# Mircophone_Module_Sch_9-8-21.net
KiCad netlist of a schematic drawn in Altium Designer
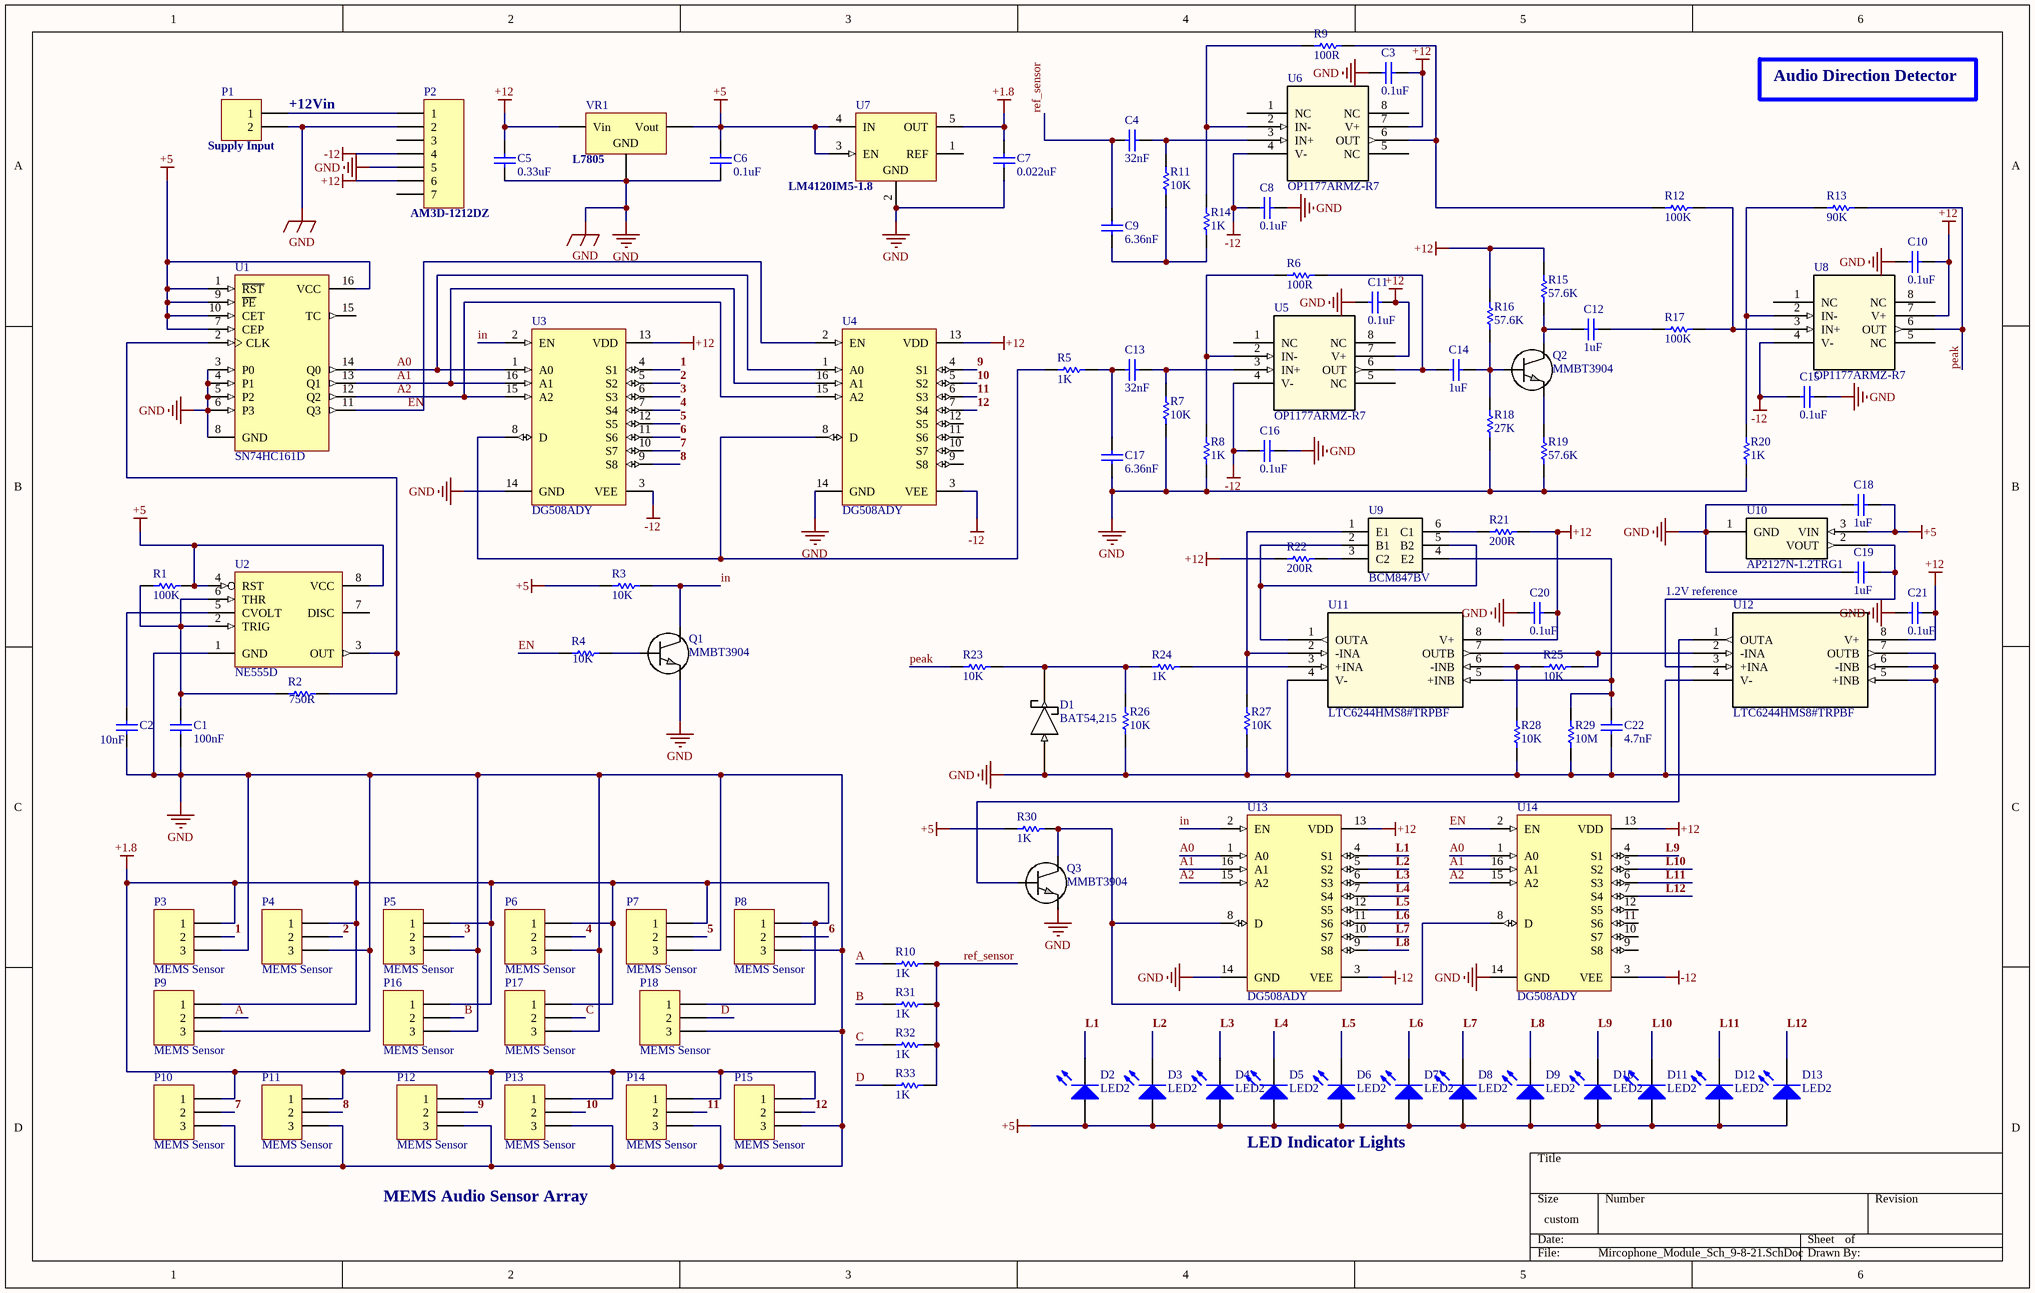
[diagram p0: Mircophone_Module_Sch_9-8-21.SchDoc]

(export (version "E")
  (design (tool "Eeschema 10.0.6"))
  (components
    (comp (ref "C1")
      (value "100nF")
      (footprint "C1206")
      (fields (field (name "PUBLISHER") "Altium Limited"))
      (libsource (lib "Miscellaneous Devices") (part "Cap Semi"))
    )
    (comp (ref "C2")
      (value "10nF")
      (footprint "C1206")
      (fields (field (name "PUBLISHER") "Altium Limited"))
      (libsource (lib "Miscellaneous Devices") (part "Cap Semi"))
    )
    (comp (ref "C3")
      (value "0.1uF")
      (footprint "C1206")
      (fields (field (name "PUBLISHER") "Altium Limited"))
      (libsource (lib "Miscellaneous Devices") (part "Cap Semi"))
    )
    (comp (ref "C4")
      (value "32nF")
      (footprint "C1206")
      (fields (field (name "PUBLISHER") "Altium Limited"))
      (libsource (lib "Miscellaneous Devices") (part "Cap Semi"))
    )
    (comp (ref "C5")
      (value "0.33uF")
      (footprint "C1206")
      (fields (field (name "PUBLISHER") "Altium Limited"))
      (libsource (lib "Miscellaneous Devices") (part "Cap Semi"))
    )
    (comp (ref "C6")
      (value "0.1uF")
      (footprint "C1206")
      (fields (field (name "PUBLISHER") "Altium Limited"))
      (libsource (lib "Miscellaneous Devices") (part "Cap Semi"))
    )
    (comp (ref "C7")
      (value "0.022uF")
      (footprint "C1206")
      (fields (field (name "PUBLISHER") "Altium Limited"))
      (libsource (lib "Miscellaneous Devices") (part "Cap Semi"))
    )
    (comp (ref "C8")
      (value "0.1uF")
      (footprint "C1206")
      (fields (field (name "PUBLISHER") "Altium Limited"))
      (libsource (lib "Miscellaneous Devices") (part "Cap Semi"))
    )
    (comp (ref "C9")
      (value "6.36nF")
      (footprint "C1206")
      (fields (field (name "PUBLISHER") "Altium Limited"))
      (libsource (lib "Miscellaneous Devices") (part "Cap Semi"))
    )
    (comp (ref "C10")
      (value "0.1uF")
      (footprint "C1206")
      (fields (field (name "PUBLISHER") "Altium Limited"))
      (libsource (lib "Miscellaneous Devices") (part "Cap Semi"))
    )
    (comp (ref "C11")
      (value "0.1uF")
      (footprint "C1206")
      (fields (field (name "PUBLISHER") "Altium Limited"))
      (libsource (lib "Miscellaneous Devices") (part "Cap Semi"))
    )
    (comp (ref "C12")
      (value "1uF")
      (footprint "C1206")
      (fields (field (name "PUBLISHER") "Altium Limited"))
      (libsource (lib "Miscellaneous Devices") (part "Cap Semi"))
    )
    (comp (ref "C13")
      (value "32nF")
      (footprint "C1206")
      (fields (field (name "PUBLISHER") "Altium Limited"))
      (libsource (lib "Miscellaneous Devices") (part "Cap Semi"))
    )
    (comp (ref "C14")
      (value "1uF")
      (footprint "C1206")
      (fields (field (name "PUBLISHER") "Altium Limited"))
      (libsource (lib "Miscellaneous Devices") (part "Cap Semi"))
    )
    (comp (ref "C15")
      (value "0.1uF")
      (footprint "C1206")
      (fields (field (name "PUBLISHER") "Altium Limited"))
      (libsource (lib "Miscellaneous Devices") (part "Cap Semi"))
    )
    (comp (ref "C16")
      (value "0.1uF")
      (footprint "C1206")
      (fields (field (name "PUBLISHER") "Altium Limited"))
      (libsource (lib "Miscellaneous Devices") (part "Cap Semi"))
    )
    (comp (ref "C17")
      (value "6.36nF")
      (footprint "C1206")
      (fields (field (name "PUBLISHER") "Altium Limited"))
      (libsource (lib "Miscellaneous Devices") (part "Cap Semi"))
    )
    (comp (ref "C18")
      (value "1uF")
      (footprint "C1206")
      (fields (field (name "PUBLISHER") "Altium Limited"))
      (libsource (lib "Miscellaneous Devices") (part "Cap Semi"))
    )
    (comp (ref "C19")
      (value "1uF")
      (footprint "C1206")
      (fields (field (name "PUBLISHER") "Altium Limited"))
      (libsource (lib "Miscellaneous Devices") (part "Cap Semi"))
    )
    (comp (ref "C20")
      (value "0.1uF")
      (footprint "C1206")
      (fields (field (name "PUBLISHER") "Altium Limited"))
      (libsource (lib "Miscellaneous Devices") (part "Cap Semi"))
    )
    (comp (ref "C21")
      (value "0.1uF")
      (footprint "C1206")
      (fields (field (name "PUBLISHER") "Altium Limited"))
      (libsource (lib "Miscellaneous Devices") (part "Cap Semi"))
    )
    (comp (ref "C22")
      (value "4.7nF")
      (footprint "C1206")
      (fields (field (name "PUBLISHER") "Altium Limited"))
      (libsource (lib "Miscellaneous Devices") (part "Cap Semi"))
    )
    (comp (ref "D1")
      (value "BAT54,215")
      (footprint "SOT95P230X110-3N")
      (description "No Description Available")
      (fields (field (name "COPYRIGHT") "Copyright (C) 2021 Ultra Librarian. All rights reserved."))
      (libsource (lib "BAT54,215") (part "BAT54,215"))
    )
    (comp (ref "D2")
      (value "LED2")
      (footprint "0603")
      (description "Typical RED, GREEN, YELLOW, AMBER GaAs LED")
      (fields (field (name "PUBLISHER") "Altium Limited"))
      (libsource (lib "Miscellaneous Devices") (part "LED2"))
    )
    (comp (ref "D3")
      (value "LED2")
      (footprint "0603")
      (description "Typical RED, GREEN, YELLOW, AMBER GaAs LED")
      (fields (field (name "PUBLISHER") "Altium Limited"))
      (libsource (lib "Miscellaneous Devices") (part "LED2"))
    )
    (comp (ref "D4")
      (value "LED2")
      (footprint "0603")
      (description "Typical RED, GREEN, YELLOW, AMBER GaAs LED")
      (fields (field (name "PUBLISHER") "Altium Limited"))
      (libsource (lib "Miscellaneous Devices") (part "LED2"))
    )
    (comp (ref "D5")
      (value "LED2")
      (footprint "0603")
      (description "Typical RED, GREEN, YELLOW, AMBER GaAs LED")
      (fields (field (name "PUBLISHER") "Altium Limited"))
      (libsource (lib "Miscellaneous Devices") (part "LED2"))
    )
    (comp (ref "D6")
      (value "LED2")
      (footprint "0603")
      (description "Typical RED, GREEN, YELLOW, AMBER GaAs LED")
      (fields (field (name "PUBLISHER") "Altium Limited"))
      (libsource (lib "Miscellaneous Devices") (part "LED2"))
    )
    (comp (ref "D7")
      (value "LED2")
      (footprint "0603")
      (description "Typical RED, GREEN, YELLOW, AMBER GaAs LED")
      (fields (field (name "PUBLISHER") "Altium Limited"))
      (libsource (lib "Miscellaneous Devices") (part "LED2"))
    )
    (comp (ref "D8")
      (value "LED2")
      (footprint "0603")
      (description "Typical RED, GREEN, YELLOW, AMBER GaAs LED")
      (fields (field (name "PUBLISHER") "Altium Limited"))
      (libsource (lib "Miscellaneous Devices") (part "LED2"))
    )
    (comp (ref "D9")
      (value "LED2")
      (footprint "0603")
      (description "Typical RED, GREEN, YELLOW, AMBER GaAs LED")
      (fields (field (name "PUBLISHER") "Altium Limited"))
      (libsource (lib "Miscellaneous Devices") (part "LED2"))
    )
    (comp (ref "D10")
      (value "LED2")
      (footprint "0603")
      (description "Typical RED, GREEN, YELLOW, AMBER GaAs LED")
      (fields (field (name "PUBLISHER") "Altium Limited"))
      (libsource (lib "Miscellaneous Devices") (part "LED2"))
    )
    (comp (ref "D11")
      (value "LED2")
      (footprint "0603")
      (description "Typical RED, GREEN, YELLOW, AMBER GaAs LED")
      (fields (field (name "PUBLISHER") "Altium Limited"))
      (libsource (lib "Miscellaneous Devices") (part "LED2"))
    )
    (comp (ref "D12")
      (value "LED2")
      (footprint "0603")
      (description "Typical RED, GREEN, YELLOW, AMBER GaAs LED")
      (fields (field (name "PUBLISHER") "Altium Limited"))
      (libsource (lib "Miscellaneous Devices") (part "LED2"))
    )
    (comp (ref "D13")
      (value "LED2")
      (footprint "0603")
      (description "Typical RED, GREEN, YELLOW, AMBER GaAs LED")
      (fields (field (name "PUBLISHER") "Altium Limited"))
      (libsource (lib "Miscellaneous Devices") (part "LED2"))
    )
    (comp (ref "P1")
      (value "Supply Input")
      (footprint "HDR1X2")
      (description "Header, 2-Pin")
      (fields (field (name "PUBLISHER") "Altium Limited"))
      (libsource (lib "Miscellaneous Connectors") (part "Header 2"))
    )
    (comp (ref "P2")
      (value "AM3D-1212DZ")
      (footprint "HDR1X7")
      (description "3 Watt ¦ DC-DC Converter Dual 1000VDC isolation")
      (fields (field (name "PUBLISHER") "Altium Limited"))
      (libsource (lib "Miscellaneous Connectors") (part "Header 7"))
    )
    (comp (ref "P3")
      (value "MEMS Sensor")
      (footprint "MIC_ICS-43434")
      (description "MMICT4076-00-908")
      (fields (field (name "PUBLISHER") "Altium Limited"))
      (libsource (lib "Miscellaneous Connectors") (part "Header 3"))
    )
    (comp (ref "P4")
      (value "MEMS Sensor")
      (footprint "MIC_ICS-43434")
      (description "MMICT4076-00-908")
      (fields (field (name "PUBLISHER") "Altium Limited"))
      (libsource (lib "Miscellaneous Connectors") (part "Header 3"))
    )
    (comp (ref "P5")
      (value "MEMS Sensor")
      (footprint "MIC_ICS-43434")
      (description "MMICT4076-00-908")
      (fields (field (name "PUBLISHER") "Altium Limited"))
      (libsource (lib "Miscellaneous Connectors") (part "Header 3"))
    )
    (comp (ref "P6")
      (value "MEMS Sensor")
      (footprint "MIC_ICS-43434")
      (description "MMICT4076-00-908")
      (fields (field (name "PUBLISHER") "Altium Limited"))
      (libsource (lib "Miscellaneous Connectors") (part "Header 3"))
    )
    (comp (ref "P7")
      (value "MEMS Sensor")
      (footprint "MIC_ICS-43434")
      (description "MMICT4076-00-908")
      (fields (field (name "PUBLISHER") "Altium Limited"))
      (libsource (lib "Miscellaneous Connectors") (part "Header 3"))
    )
    (comp (ref "P8")
      (value "MEMS Sensor")
      (footprint "MIC_ICS-43434")
      (description "MMICT4076-00-908")
      (fields (field (name "PUBLISHER") "Altium Limited"))
      (libsource (lib "Miscellaneous Connectors") (part "Header 3"))
    )
    (comp (ref "P9")
      (value "MEMS Sensor")
      (footprint "MIC_ICS-43434")
      (description "MMICT4076-00-908")
      (fields (field (name "PUBLISHER") "Altium Limited"))
      (libsource (lib "Miscellaneous Connectors") (part "Header 3"))
    )
    (comp (ref "P10")
      (value "MEMS Sensor")
      (footprint "MIC_ICS-43434")
      (description "MMICT4076-00-908")
      (fields (field (name "PUBLISHER") "Altium Limited"))
      (libsource (lib "Miscellaneous Connectors") (part "Header 3"))
    )
    (comp (ref "P11")
      (value "MEMS Sensor")
      (footprint "MIC_ICS-43434")
      (description "MMICT4076-00-908")
      (fields (field (name "PUBLISHER") "Altium Limited"))
      (libsource (lib "Miscellaneous Connectors") (part "Header 3"))
    )
    (comp (ref "P12")
      (value "MEMS Sensor")
      (footprint "MIC_ICS-43434")
      (description "MMICT4076-00-908")
      (fields (field (name "PUBLISHER") "Altium Limited"))
      (libsource (lib "Miscellaneous Connectors") (part "Header 3"))
    )
    (comp (ref "P13")
      (value "MEMS Sensor")
      (footprint "MIC_ICS-43434")
      (description "MMICT4076-00-908")
      (fields (field (name "PUBLISHER") "Altium Limited"))
      (libsource (lib "Miscellaneous Connectors") (part "Header 3"))
    )
    (comp (ref "P14")
      (value "MEMS Sensor")
      (footprint "MIC_ICS-43434")
      (description "MMICT4076-00-908")
      (fields (field (name "PUBLISHER") "Altium Limited"))
      (libsource (lib "Miscellaneous Connectors") (part "Header 3"))
    )
    (comp (ref "P15")
      (value "MEMS Sensor")
      (footprint "MIC_ICS-43434")
      (description "MMICT4076-00-908")
      (fields (field (name "PUBLISHER") "Altium Limited"))
      (libsource (lib "Miscellaneous Connectors") (part "Header 3"))
    )
    (comp (ref "P16")
      (value "MEMS Sensor")
      (footprint "MIC_ICS-43434")
      (description "MMICT4076-00-908")
      (fields (field (name "PUBLISHER") "Altium Limited"))
      (libsource (lib "Miscellaneous Connectors") (part "Header 3"))
    )
    (comp (ref "P17")
      (value "MEMS Sensor")
      (footprint "MIC_ICS-43434")
      (description "MMICT4076-00-908")
      (fields (field (name "PUBLISHER") "Altium Limited"))
      (libsource (lib "Miscellaneous Connectors") (part "Header 3"))
    )
    (comp (ref "P18")
      (value "MEMS Sensor")
      (footprint "MIC_ICS-43434")
      (description "MMICT4076-00-908")
      (fields (field (name "PUBLISHER") "Altium Limited"))
      (libsource (lib "Miscellaneous Connectors") (part "Header 3"))
    )
    (comp (ref "Q1")
      (value "MMBT3904")
      (footprint "SOT95P230X110-3N")
      (description "No Description Available")
      (fields (field (name "COPYRIGHT") "Copyright (C) 2021 Ultra Librarian. All rights reserved."))
      (libsource (lib "MMBT3904") (part "MMBT3904"))
    )
    (comp (ref "Q2")
      (value "MMBT3904")
      (footprint "SOT95P230X110-3N")
      (description "No Description Available")
      (fields (field (name "COPYRIGHT") "Copyright (C) 2021 Ultra Librarian. All rights reserved."))
      (libsource (lib "MMBT3904") (part "MMBT3904"))
    )
    (comp (ref "Q3")
      (value "MMBT3904")
      (footprint "SOT95P230X110-3N")
      (description "No Description Available")
      (fields (field (name "COPYRIGHT") "Copyright (C) 2021 Ultra Librarian. All rights reserved."))
      (libsource (lib "MMBT3904") (part "MMBT3904"))
    )
    (comp (ref "R1")
      (value "100K")
      (footprint "6-0805_N")
      (description "Resistor")
      (fields (field (name "PUBLISHER") "Altium Limited"))
      (libsource (lib "Miscellaneous Devices") (part "Res1"))
    )
    (comp (ref "R2")
      (value "750R")
      (footprint "6-0805_N")
      (description "Resistor")
      (fields (field (name "PUBLISHER") "Altium Limited"))
      (libsource (lib "Miscellaneous Devices") (part "Res1"))
    )
    (comp (ref "R3")
      (value "10K")
      (footprint "6-0805_N")
      (description "Resistor")
      (fields (field (name "PUBLISHER") "Altium Limited"))
      (libsource (lib "Miscellaneous Devices") (part "Res1"))
    )
    (comp (ref "R4")
      (value "10K")
      (footprint "6-0805_N")
      (description "Resistor")
      (fields (field (name "PUBLISHER") "Altium Limited"))
      (libsource (lib "Miscellaneous Devices") (part "Res1"))
    )
    (comp (ref "R5")
      (value "1K")
      (footprint "6-0805_N")
      (description "Resistor")
      (fields (field (name "PUBLISHER") "Altium Limited"))
      (libsource (lib "Miscellaneous Devices") (part "Res1"))
    )
    (comp (ref "R6")
      (value "100R")
      (footprint "6-0805_N")
      (description "Resistor")
      (fields (field (name "PUBLISHER") "Altium Limited"))
      (libsource (lib "Miscellaneous Devices") (part "Res1"))
    )
    (comp (ref "R7")
      (value "10K")
      (footprint "6-0805_N")
      (description "Resistor")
      (fields (field (name "PUBLISHER") "Altium Limited"))
      (libsource (lib "Miscellaneous Devices") (part "Res1"))
    )
    (comp (ref "R8")
      (value "1K")
      (footprint "6-0805_N")
      (description "Resistor")
      (fields (field (name "PUBLISHER") "Altium Limited"))
      (libsource (lib "Miscellaneous Devices") (part "Res1"))
    )
    (comp (ref "R9")
      (value "100R")
      (footprint "6-0805_N")
      (description "Resistor")
      (fields (field (name "PUBLISHER") "Altium Limited"))
      (libsource (lib "Miscellaneous Devices") (part "Res1"))
    )
    (comp (ref "R10")
      (value "1K")
      (footprint "6-0805_N")
      (description "Resistor")
      (fields (field (name "PUBLISHER") "Altium Limited"))
      (libsource (lib "Miscellaneous Devices") (part "Res1"))
    )
    (comp (ref "R11")
      (value "10K")
      (footprint "6-0805_N")
      (description "Resistor")
      (fields (field (name "PUBLISHER") "Altium Limited"))
      (libsource (lib "Miscellaneous Devices") (part "Res1"))
    )
    (comp (ref "R12")
      (value "100K")
      (footprint "6-0805_N")
      (description "Resistor")
      (fields (field (name "PUBLISHER") "Altium Limited"))
      (libsource (lib "Miscellaneous Devices") (part "Res1"))
    )
    (comp (ref "R13")
      (value "90K")
      (footprint "6-0805_N")
      (description "Resistor")
      (fields (field (name "PUBLISHER") "Altium Limited"))
      (libsource (lib "Miscellaneous Devices") (part "Res1"))
    )
    (comp (ref "R14")
      (value "1K")
      (footprint "6-0805_N")
      (description "Resistor")
      (fields (field (name "PUBLISHER") "Altium Limited"))
      (libsource (lib "Miscellaneous Devices") (part "Res1"))
    )
    (comp (ref "R15")
      (value "57.6K")
      (footprint "6-0805_N")
      (description "Resistor")
      (fields (field (name "PUBLISHER") "Altium Limited"))
      (libsource (lib "Miscellaneous Devices") (part "Res1"))
    )
    (comp (ref "R16")
      (value "57.6K")
      (footprint "6-0805_N")
      (description "Resistor")
      (fields (field (name "PUBLISHER") "Altium Limited"))
      (libsource (lib "Miscellaneous Devices") (part "Res1"))
    )
    (comp (ref "R17")
      (value "100K")
      (footprint "6-0805_N")
      (description "Resistor")
      (fields (field (name "PUBLISHER") "Altium Limited"))
      (libsource (lib "Miscellaneous Devices") (part "Res1"))
    )
    (comp (ref "R18")
      (value "27K")
      (footprint "6-0805_N")
      (description "Resistor")
      (fields (field (name "PUBLISHER") "Altium Limited"))
      (libsource (lib "Miscellaneous Devices") (part "Res1"))
    )
    (comp (ref "R19")
      (value "57.6K")
      (footprint "6-0805_N")
      (description "Resistor")
      (fields (field (name "PUBLISHER") "Altium Limited"))
      (libsource (lib "Miscellaneous Devices") (part "Res1"))
    )
    (comp (ref "R20")
      (value "1K")
      (footprint "6-0805_N")
      (description "Resistor")
      (fields (field (name "PUBLISHER") "Altium Limited"))
      (libsource (lib "Miscellaneous Devices") (part "Res1"))
    )
    (comp (ref "R21")
      (value "200R")
      (footprint "6-0805_N")
      (description "Resistor")
      (fields (field (name "PUBLISHER") "Altium Limited"))
      (libsource (lib "Miscellaneous Devices") (part "Res1"))
    )
    (comp (ref "R22")
      (value "200R")
      (footprint "6-0805_N")
      (description "Resistor")
      (fields (field (name "PUBLISHER") "Altium Limited"))
      (libsource (lib "Miscellaneous Devices") (part "Res1"))
    )
    (comp (ref "R23")
      (value "10K")
      (footprint "6-0805_N")
      (description "Resistor")
      (fields (field (name "PUBLISHER") "Altium Limited"))
      (libsource (lib "Miscellaneous Devices") (part "Res1"))
    )
    (comp (ref "R24")
      (value "1K")
      (footprint "6-0805_N")
      (description "Resistor")
      (fields (field (name "PUBLISHER") "Altium Limited"))
      (libsource (lib "Miscellaneous Devices") (part "Res1"))
    )
    (comp (ref "R25")
      (value "10K")
      (footprint "6-0805_N")
      (description "Resistor")
      (fields (field (name "PUBLISHER") "Altium Limited"))
      (libsource (lib "Miscellaneous Devices") (part "Res1"))
    )
    (comp (ref "R26")
      (value "10K")
      (footprint "6-0805_N")
      (description "Resistor")
      (fields (field (name "PUBLISHER") "Altium Limited"))
      (libsource (lib "Miscellaneous Devices") (part "Res1"))
    )
    (comp (ref "R27")
      (value "10K")
      (footprint "6-0805_N")
      (description "Resistor")
      (fields (field (name "PUBLISHER") "Altium Limited"))
      (libsource (lib "Miscellaneous Devices") (part "Res1"))
    )
    (comp (ref "R28")
      (value "10K")
      (footprint "6-0805_N")
      (description "Resistor")
      (fields (field (name "PUBLISHER") "Altium Limited"))
      (libsource (lib "Miscellaneous Devices") (part "Res1"))
    )
    (comp (ref "R29")
      (value "10M")
      (footprint "6-0805_N")
      (description "Resistor")
      (fields (field (name "PUBLISHER") "Altium Limited"))
      (libsource (lib "Miscellaneous Devices") (part "Res1"))
    )
    (comp (ref "R30")
      (value "1K")
      (footprint "6-0805_N")
      (description "Resistor")
      (fields (field (name "PUBLISHER") "Altium Limited"))
      (libsource (lib "Miscellaneous Devices") (part "Res1"))
    )
    (comp (ref "R31")
      (value "1K")
      (footprint "6-0805_N")
      (description "Resistor")
      (fields (field (name "PUBLISHER") "Altium Limited"))
      (libsource (lib "Miscellaneous Devices") (part "Res1"))
    )
    (comp (ref "R32")
      (value "1K")
      (footprint "6-0805_N")
      (description "Resistor")
      (fields (field (name "PUBLISHER") "Altium Limited"))
      (libsource (lib "Miscellaneous Devices") (part "Res1"))
    )
    (comp (ref "R33")
      (value "1K")
      (footprint "6-0805_N")
      (description "Resistor")
      (fields (field (name "PUBLISHER") "Altium Limited"))
      (libsource (lib "Miscellaneous Devices") (part "Res1"))
    )
    (comp (ref "U1")
      (value "SN74HC161D")
      (footprint "SOIC127P600X175-16N")
      (description "4-Bit Synchronous Binary Counter")
      (fields (field (name "PUBLISHER") "Altium Limited"))
      (libsource (lib "TI Logic Counter") (part "SN74HC161D"))
    )
    (comp (ref "U2")
      (value "NE555D")
      (footprint "SOIC127P599X175-8N")
      (description "General-Purpose Single Bipolar Timer")
      (fields (field (name "PUBLISHER") "Altium Limited"))
      (libsource (lib "ST Analog Timer Circuit") (part "NE555D"))
    )
    (comp (ref "U3")
      (value "DG508ADY")
      (footprint "SOIC127P600X175-16N")
      (description "Monolithic CMOS Analog Multiplexer")
      (fields (field (name "PUBLISHER") "Altium Limited"))
      (libsource (lib "Maxim Logic Multiplexer") (part "DG508ADY"))
    )
    (comp (ref "U4")
      (value "DG508ADY")
      (footprint "SOIC127P600X175-16N")
      (description "Monolithic CMOS Analog Multiplexer")
      (fields (field (name "PUBLISHER") "Altium Limited"))
      (libsource (lib "Maxim Logic Multiplexer") (part "DG508ADY"))
    )
    (comp (ref "U5")
      (value "OP1177ARMZ-R7")
      (footprint "SOP65P490X110-8N")
      (description "No Description Available")
      (fields (field (name "COPYRIGHT") "Copyright (C) 2021 Ultra Librarian. All rights reserved."))
      (libsource (lib "OP1177ARMZ-R7") (part "OP1177ARMZ-R7"))
    )
    (comp (ref "U6")
      (value "OP1177ARMZ-R7")
      (footprint "SOP65P490X110-8N")
      (description "No Description Available")
      (fields (field (name "COPYRIGHT") "Copyright (C) 2021 Ultra Librarian. All rights reserved."))
      (libsource (lib "OP1177ARMZ-R7") (part "OP1177ARMZ-R7"))
    )
    (comp (ref "U7")
      (value "LM4120IM5-1.8")
      (footprint "SOT95P285X120-5N")
      (description "Precision Micropower Low Dropout Voltage Reference, 5-pin SOT-23")
      (fields
        (field (name "MANUFACTURER") "National Semiconductor")
        (field (name "PUBLISHER") "Altium Limited")
      )
      (libsource (lib "NSC Voltage Reference") (part "LM4120IM5-1.8"))
    )
    (comp (ref "U8")
      (value "OP1177ARMZ-R7")
      (footprint "SOP65P490X110-8N")
      (description "No Description Available")
      (fields (field (name "COPYRIGHT") "Copyright (C) 2021 Ultra Librarian. All rights reserved."))
      (libsource (lib "OP1177ARMZ-R7") (part "OP1177ARMZ-R7"))
    )
    (comp (ref "U9")
      (value "BCM847BV")
      (footprint "SOT50P160X60-6N")
      (description "No Description Available")
      (fields (field (name "COPYRIGHT") "Copyright (C) 2021 Ultra Librarian. All rights reserved."))
      (libsource (lib "BCM847BV") (part "BCM847BV"))
    )
    (comp (ref "U10")
      (value "AP2127N-1.2TRG1")
      (footprint "SOT91P240X110-3N")
      (description "No Description Available")
      (fields
        (field (name "MANUFACTURER_PART_NUMBER") "AP2127N-1.8TRG1")
        (field (name "COPYRIGHT") "Copyright (C) 2021 Ultra Librarian. All rights reserved.")
      )
      (libsource (lib "AP2127N-1P8TRG1") (part "AP2127N-1.8TRG1"))
    )
    (comp (ref "U11")
      (value "LTC6244HMS8#TRPBF")
      (footprint "MSOP-8_MS")
      (description "No Description Available")
      (fields (field (name "COPYRIGHT") "Copyright (C) 2021 Ultra Librarian. All rights reserved."))
      (libsource (lib "LTC6244HMS8&hash_TRPBF") (part "LTC6244HMS8#TRPBF"))
    )
    (comp (ref "U12")
      (value "LTC6244HMS8#TRPBF")
      (footprint "MSOP-8_MS")
      (description "No Description Available")
      (fields (field (name "COPYRIGHT") "Copyright (C) 2021 Ultra Librarian. All rights reserved."))
      (libsource (lib "LTC6244HMS8&hash_TRPBF") (part "LTC6244HMS8#TRPBF"))
    )
    (comp (ref "U13")
      (value "DG508ADY")
      (footprint "SOIC127P600X175-16N")
      (description "Monolithic CMOS Analog Multiplexer")
      (fields (field (name "PUBLISHER") "Altium Limited"))
      (libsource (lib "Maxim Logic Multiplexer") (part "DG508ADY"))
    )
    (comp (ref "U14")
      (value "DG508ADY")
      (footprint "SOIC127P600X175-16N")
      (description "Monolithic CMOS Analog Multiplexer")
      (fields (field (name "PUBLISHER") "Altium Limited"))
      (libsource (lib "Maxim Logic Multiplexer") (part "DG508ADY"))
    )
    (comp (ref "VR1")
      (value "L7805")
      (footprint "D2PAK_N")
      (description "Voltage Regulator")
      (fields (field (name "PUBLISHER") "Altium Limited"))
      (libsource (lib "Miscellaneous Devices") (part "Volt Reg"))
    )
  )
  (nets
    (net (code "1") (name "+1.8") (class "Default")
      (node (ref "C7") (pin "2") (pinfunction "2_2") (pintype "passive"))
      (node (ref "P10") (pin "1") (pinfunction "1_1") (pintype "passive"))
      (node (ref "P11") (pin "1") (pinfunction "1_1") (pintype "passive"))
      (node (ref "P12") (pin "1") (pinfunction "1_1") (pintype "passive"))
      (node (ref "P13") (pin "1") (pinfunction "1_1") (pintype "passive"))
      (node (ref "P14") (pin "1") (pinfunction "1_1") (pintype "passive"))
      (node (ref "P15") (pin "1") (pinfunction "1_1") (pintype "passive"))
      (node (ref "P16") (pin "1") (pinfunction "1_1") (pintype "passive"))
      (node (ref "P17") (pin "1") (pinfunction "1_1") (pintype "passive"))
      (node (ref "P18") (pin "1") (pinfunction "1_1") (pintype "passive"))
      (node (ref "P3") (pin "1") (pinfunction "1_1") (pintype "passive"))
      (node (ref "P4") (pin "1") (pinfunction "1_1") (pintype "passive"))
      (node (ref "P5") (pin "1") (pinfunction "1_1") (pintype "passive"))
      (node (ref "P6") (pin "1") (pinfunction "1_1") (pintype "passive"))
      (node (ref "P7") (pin "1") (pinfunction "1_1") (pintype "passive"))
      (node (ref "P8") (pin "1") (pinfunction "1_1") (pintype "passive"))
      (node (ref "P9") (pin "1") (pinfunction "1_1") (pintype "passive"))
      (node (ref "U7") (pin "5") (pinfunction "OUT_5") (pintype "power_in"))
    )
    (net (code "2") (name "+5") (class "Default")
      (node (ref "C18") (pin "2") (pinfunction "2_2") (pintype "passive"))
      (node (ref "C6") (pin "2") (pinfunction "2_2") (pintype "passive"))
      (node (ref "D10") (pin "1") (pinfunction "A_1") (pintype "passive"))
      (node (ref "D11") (pin "1") (pinfunction "A_1") (pintype "passive"))
      (node (ref "D12") (pin "1") (pinfunction "A_1") (pintype "passive"))
      (node (ref "D13") (pin "1") (pinfunction "A_1") (pintype "passive"))
      (node (ref "D2") (pin "1") (pinfunction "A_1") (pintype "passive"))
      (node (ref "D3") (pin "1") (pinfunction "A_1") (pintype "passive"))
      (node (ref "D4") (pin "1") (pinfunction "A_1") (pintype "passive"))
      (node (ref "D5") (pin "1") (pinfunction "A_1") (pintype "passive"))
      (node (ref "D6") (pin "1") (pinfunction "A_1") (pintype "passive"))
      (node (ref "D7") (pin "1") (pinfunction "A_1") (pintype "passive"))
      (node (ref "D8") (pin "1") (pinfunction "A_1") (pintype "passive"))
      (node (ref "D9") (pin "1") (pinfunction "A_1") (pintype "passive"))
      (node (ref "R1") (pin "2") (pinfunction "2_2") (pintype "passive"))
      (node (ref "R3") (pin "2") (pinfunction "2_2") (pintype "passive"))
      (node (ref "R30") (pin "1") (pinfunction "1_1") (pintype "passive"))
      (node (ref "U1") (pin "1") (pinfunction "~{RST}_1") (pintype "input"))
      (node (ref "U1") (pin "10") (pinfunction "CET_10") (pintype "input"))
      (node (ref "U1") (pin "16") (pinfunction "VCC_16") (pintype "power_in"))
      (node (ref "U1") (pin "7") (pinfunction "CEP_7") (pintype "input"))
      (node (ref "U1") (pin "9") (pinfunction "~{PE}_9") (pintype "input"))
      (node (ref "U10") (pin "3") (pinfunction "VIN_3") (pintype "input"))
      (node (ref "U2") (pin "4") (pinfunction "RST_4") (pintype "input"))
      (node (ref "U2") (pin "8") (pinfunction "VCC_8") (pintype "power_in"))
      (node (ref "U7") (pin "3") (pinfunction "EN_3") (pintype "input"))
      (node (ref "U7") (pin "4") (pinfunction "IN_4") (pintype "power_in"))
      (node (ref "VR1") (pin "3") (pinfunction "Vout_3") (pintype "passive"))
    )
    (net (code "3") (name "+12") (class "Default")
      (node (ref "C10") (pin "2") (pinfunction "2_2") (pintype "passive"))
      (node (ref "C11") (pin "2") (pinfunction "2_2") (pintype "passive"))
      (node (ref "C20") (pin "1") (pinfunction "1_1") (pintype "passive"))
      (node (ref "C21") (pin "1") (pinfunction "1_1") (pintype "passive"))
      (node (ref "C3") (pin "2") (pinfunction "2_2") (pintype "passive"))
      (node (ref "C5") (pin "2") (pinfunction "2_2") (pintype "passive"))
      (node (ref "P2") (pin "6") (pinfunction "6_6") (pintype "passive"))
      (node (ref "R15") (pin "1") (pinfunction "1_1") (pintype "passive"))
      (node (ref "R16") (pin "1") (pinfunction "1_1") (pintype "passive"))
      (node (ref "R21") (pin "2") (pinfunction "2_2") (pintype "passive"))
      (node (ref "R22") (pin "1") (pinfunction "1_1") (pintype "passive"))
      (node (ref "U11") (pin "8") (pinfunction "V+_8") (pintype "power_in"))
      (node (ref "U12") (pin "8") (pinfunction "V+_8") (pintype "power_in"))
      (node (ref "U13") (pin "13") (pinfunction "VDD_13") (pintype "power_in"))
      (node (ref "U14") (pin "13") (pinfunction "VDD_13") (pintype "power_in"))
      (node (ref "U3") (pin "13") (pinfunction "VDD_13") (pintype "power_in"))
      (node (ref "U4") (pin "13") (pinfunction "VDD_13") (pintype "power_in"))
      (node (ref "U5") (pin "7") (pinfunction "V+_7") (pintype "power_in"))
      (node (ref "U6") (pin "7") (pinfunction "V+_7") (pintype "power_in"))
      (node (ref "U8") (pin "7") (pinfunction "V+_7") (pintype "power_in"))
      (node (ref "VR1") (pin "1") (pinfunction "Vin_1") (pintype "passive"))
    )
    (net (code "4") (name "-12") (class "Default")
      (node (ref "C15") (pin "1") (pinfunction "1_1") (pintype "passive"))
      (node (ref "C16") (pin "2") (pinfunction "2_2") (pintype "passive"))
      (node (ref "C8") (pin "2") (pinfunction "2_2") (pintype "passive"))
      (node (ref "P2") (pin "4") (pinfunction "4_4") (pintype "passive"))
      (node (ref "U13") (pin "3") (pinfunction "VEE_3") (pintype "power_in"))
      (node (ref "U14") (pin "3") (pinfunction "VEE_3") (pintype "power_in"))
      (node (ref "U3") (pin "3") (pinfunction "VEE_3") (pintype "power_in"))
      (node (ref "U4") (pin "3") (pinfunction "VEE_3") (pintype "power_in"))
      (node (ref "U5") (pin "4") (pinfunction "V-_4") (pintype "power_in"))
      (node (ref "U6") (pin "4") (pinfunction "V-_4") (pintype "power_in"))
      (node (ref "U8") (pin "4") (pinfunction "V-_4") (pintype "power_in"))
    )
    (net (code "5") (name "/1") (class "Default")
      (node (ref "P3") (pin "2") (pinfunction "2_2") (pintype "passive"))
      (node (ref "U3") (pin "4") (pinfunction "S1_4") (pintype "bidirectional"))
    )
    (net (code "6") (name "/2") (class "Default")
      (node (ref "P4") (pin "2") (pinfunction "2_2") (pintype "passive"))
      (node (ref "U3") (pin "5") (pinfunction "S2_5") (pintype "bidirectional"))
    )
    (net (code "7") (name "/3") (class "Default")
      (node (ref "P5") (pin "2") (pinfunction "2_2") (pintype "passive"))
      (node (ref "U3") (pin "6") (pinfunction "S3_6") (pintype "bidirectional"))
    )
    (net (code "8") (name "/4") (class "Default")
      (node (ref "P6") (pin "2") (pinfunction "2_2") (pintype "passive"))
      (node (ref "U3") (pin "7") (pinfunction "S4_7") (pintype "bidirectional"))
    )
    (net (code "9") (name "/5") (class "Default")
      (node (ref "P7") (pin "2") (pinfunction "2_2") (pintype "passive"))
      (node (ref "U3") (pin "12") (pinfunction "S5_12") (pintype "bidirectional"))
    )
    (net (code "10") (name "/6") (class "Default")
      (node (ref "P8") (pin "2") (pinfunction "2_2") (pintype "passive"))
      (node (ref "U3") (pin "11") (pinfunction "S6_11") (pintype "bidirectional"))
    )
    (net (code "11") (name "/7") (class "Default")
      (node (ref "P10") (pin "2") (pinfunction "2_2") (pintype "passive"))
      (node (ref "U3") (pin "10") (pinfunction "S7_10") (pintype "bidirectional"))
    )
    (net (code "12") (name "/8") (class "Default")
      (node (ref "P11") (pin "2") (pinfunction "2_2") (pintype "passive"))
      (node (ref "U3") (pin "9") (pinfunction "S8_9") (pintype "bidirectional"))
    )
    (net (code "13") (name "/9") (class "Default")
      (node (ref "P12") (pin "2") (pinfunction "2_2") (pintype "passive"))
      (node (ref "U4") (pin "4") (pinfunction "S1_4") (pintype "bidirectional"))
    )
    (net (code "14") (name "/10") (class "Default")
      (node (ref "P13") (pin "2") (pinfunction "2_2") (pintype "passive"))
      (node (ref "U4") (pin "5") (pinfunction "S2_5") (pintype "bidirectional"))
    )
    (net (code "15") (name "/11") (class "Default")
      (node (ref "P14") (pin "2") (pinfunction "2_2") (pintype "passive"))
      (node (ref "U4") (pin "6") (pinfunction "S3_6") (pintype "bidirectional"))
    )
    (net (code "16") (name "/12") (class "Default")
      (node (ref "P15") (pin "2") (pinfunction "2_2") (pintype "passive"))
      (node (ref "U4") (pin "7") (pinfunction "S4_7") (pintype "bidirectional"))
    )
    (net (code "17") (name "/A") (class "Default")
      (node (ref "P9") (pin "2") (pinfunction "2_2") (pintype "passive"))
      (node (ref "R10") (pin "1") (pinfunction "1_1") (pintype "passive"))
    )
    (net (code "18") (name "/A0") (class "Default")
      (node (ref "U1") (pin "14") (pinfunction "Q0_14") (pintype "output"))
      (node (ref "U13") (pin "1") (pinfunction "A0_1") (pintype "input"))
      (node (ref "U14") (pin "1") (pinfunction "A0_1") (pintype "input"))
      (node (ref "U3") (pin "1") (pinfunction "A0_1") (pintype "input"))
      (node (ref "U4") (pin "1") (pinfunction "A0_1") (pintype "input"))
    )
    (net (code "19") (name "/A1") (class "Default")
      (node (ref "U1") (pin "13") (pinfunction "Q1_13") (pintype "output"))
      (node (ref "U13") (pin "16") (pinfunction "A1_16") (pintype "input"))
      (node (ref "U14") (pin "16") (pinfunction "A1_16") (pintype "input"))
      (node (ref "U3") (pin "16") (pinfunction "A1_16") (pintype "input"))
      (node (ref "U4") (pin "16") (pinfunction "A1_16") (pintype "input"))
    )
    (net (code "20") (name "/A2") (class "Default")
      (node (ref "U1") (pin "12") (pinfunction "Q2_12") (pintype "output"))
      (node (ref "U13") (pin "15") (pinfunction "A2_15") (pintype "input"))
      (node (ref "U14") (pin "15") (pinfunction "A2_15") (pintype "input"))
      (node (ref "U3") (pin "15") (pinfunction "A2_15") (pintype "input"))
      (node (ref "U4") (pin "15") (pinfunction "A2_15") (pintype "input"))
    )
    (net (code "21") (name "/B") (class "Default")
      (node (ref "P16") (pin "2") (pinfunction "2_2") (pintype "passive"))
      (node (ref "R31") (pin "1") (pinfunction "1_1") (pintype "passive"))
    )
    (net (code "22") (name "/C") (class "Default")
      (node (ref "P17") (pin "2") (pinfunction "2_2") (pintype "passive"))
      (node (ref "R32") (pin "1") (pinfunction "1_1") (pintype "passive"))
    )
    (net (code "23") (name "/D") (class "Default")
      (node (ref "P18") (pin "2") (pinfunction "2_2") (pintype "passive"))
      (node (ref "R33") (pin "1") (pinfunction "1_1") (pintype "passive"))
    )
    (net (code "24") (name "/EN") (class "Default")
      (node (ref "R4") (pin "1") (pinfunction "1_1") (pintype "passive"))
      (node (ref "U1") (pin "11") (pinfunction "Q3_11") (pintype "output"))
      (node (ref "U14") (pin "2") (pinfunction "EN_2") (pintype "input"))
      (node (ref "U4") (pin "2") (pinfunction "EN_2") (pintype "input"))
    )
    (net (code "25") (name "/L1") (class "Default")
      (node (ref "D2") (pin "2") (pinfunction "K_2") (pintype "passive"))
      (node (ref "U13") (pin "4") (pinfunction "S1_4") (pintype "bidirectional"))
    )
    (net (code "26") (name "/L2") (class "Default")
      (node (ref "D3") (pin "2") (pinfunction "K_2") (pintype "passive"))
      (node (ref "U13") (pin "5") (pinfunction "S2_5") (pintype "bidirectional"))
    )
    (net (code "27") (name "/L3") (class "Default")
      (node (ref "D4") (pin "2") (pinfunction "K_2") (pintype "passive"))
      (node (ref "U13") (pin "6") (pinfunction "S3_6") (pintype "bidirectional"))
    )
    (net (code "28") (name "/L4") (class "Default")
      (node (ref "D5") (pin "2") (pinfunction "K_2") (pintype "passive"))
      (node (ref "U13") (pin "7") (pinfunction "S4_7") (pintype "bidirectional"))
    )
    (net (code "29") (name "/L5") (class "Default")
      (node (ref "D6") (pin "2") (pinfunction "K_2") (pintype "passive"))
      (node (ref "U13") (pin "12") (pinfunction "S5_12") (pintype "bidirectional"))
    )
    (net (code "30") (name "/L6") (class "Default")
      (node (ref "D7") (pin "2") (pinfunction "K_2") (pintype "passive"))
      (node (ref "U13") (pin "11") (pinfunction "S6_11") (pintype "bidirectional"))
    )
    (net (code "31") (name "/L7") (class "Default")
      (node (ref "D8") (pin "2") (pinfunction "K_2") (pintype "passive"))
      (node (ref "U13") (pin "10") (pinfunction "S7_10") (pintype "bidirectional"))
    )
    (net (code "32") (name "/L8") (class "Default")
      (node (ref "D9") (pin "2") (pinfunction "K_2") (pintype "passive"))
      (node (ref "U13") (pin "9") (pinfunction "S8_9") (pintype "bidirectional"))
    )
    (net (code "33") (name "/L9") (class "Default")
      (node (ref "D10") (pin "2") (pinfunction "K_2") (pintype "passive"))
      (node (ref "U14") (pin "4") (pinfunction "S1_4") (pintype "bidirectional"))
    )
    (net (code "34") (name "/L10") (class "Default")
      (node (ref "D11") (pin "2") (pinfunction "K_2") (pintype "passive"))
      (node (ref "U14") (pin "5") (pinfunction "S2_5") (pintype "bidirectional"))
    )
    (net (code "35") (name "/L11") (class "Default")
      (node (ref "D12") (pin "2") (pinfunction "K_2") (pintype "passive"))
      (node (ref "U14") (pin "6") (pinfunction "S3_6") (pintype "bidirectional"))
    )
    (net (code "36") (name "/L12") (class "Default")
      (node (ref "D13") (pin "2") (pinfunction "K_2") (pintype "passive"))
      (node (ref "U14") (pin "7") (pinfunction "S4_7") (pintype "bidirectional"))
    )
    (net (code "37") (name "/in") (class "Default")
      (node (ref "Q1") (pin "3") (pinfunction "3_3") (pintype "passive"))
      (node (ref "R3") (pin "1") (pinfunction "1_1") (pintype "passive"))
      (node (ref "U13") (pin "2") (pinfunction "EN_2") (pintype "input"))
      (node (ref "U3") (pin "2") (pinfunction "EN_2") (pintype "input"))
    )
    (net (code "38") (name "/peak") (class "Default")
      (node (ref "R13") (pin "1") (pinfunction "1_1") (pintype "passive"))
      (node (ref "R23") (pin "1") (pinfunction "1_1") (pintype "passive"))
      (node (ref "U8") (pin "6") (pinfunction "OUT_6") (pintype "output"))
    )
    (net (code "39") (name "/ref_sensor") (class "Default")
      (node (ref "C4") (pin "2") (pinfunction "2_2") (pintype "passive"))
      (node (ref "C9") (pin "2") (pinfunction "2_2") (pintype "passive"))
      (node (ref "R10") (pin "2") (pinfunction "2_2") (pintype "passive"))
      (node (ref "R31") (pin "2") (pinfunction "2_2") (pintype "passive"))
      (node (ref "R32") (pin "2") (pinfunction "2_2") (pintype "passive"))
      (node (ref "R33") (pin "2") (pinfunction "2_2") (pintype "passive"))
    )
    (net (code "40") (name "GND") (class "Default")
      (node (ref "C1") (pin "1") (pinfunction "1_1") (pintype "passive"))
      (node (ref "C10") (pin "1") (pinfunction "1_1") (pintype "passive"))
      (node (ref "C11") (pin "1") (pinfunction "1_1") (pintype "passive"))
      (node (ref "C15") (pin "2") (pinfunction "2_2") (pintype "passive"))
      (node (ref "C16") (pin "1") (pinfunction "1_1") (pintype "passive"))
      (node (ref "C17") (pin "1") (pinfunction "1_1") (pintype "passive"))
      (node (ref "C18") (pin "1") (pinfunction "1_1") (pintype "passive"))
      (node (ref "C19") (pin "1") (pinfunction "1_1") (pintype "passive"))
      (node (ref "C2") (pin "1") (pinfunction "1_1") (pintype "passive"))
      (node (ref "C20") (pin "2") (pinfunction "2_2") (pintype "passive"))
      (node (ref "C21") (pin "2") (pinfunction "2_2") (pintype "passive"))
      (node (ref "C22") (pin "2") (pinfunction "2_2") (pintype "passive"))
      (node (ref "C3") (pin "1") (pinfunction "1_1") (pintype "passive"))
      (node (ref "C5") (pin "1") (pinfunction "1_1") (pintype "passive"))
      (node (ref "C6") (pin "1") (pinfunction "1_1") (pintype "passive"))
      (node (ref "C7") (pin "1") (pinfunction "1_1") (pintype "passive"))
      (node (ref "C8") (pin "1") (pinfunction "1_1") (pintype "passive"))
      (node (ref "D1") (pin "1") (pinfunction "ANODE_1") (pintype "input"))
      (node (ref "P1") (pin "2") (pinfunction "2_2") (pintype "passive"))
      (node (ref "P10") (pin "3") (pinfunction "3_3") (pintype "passive"))
      (node (ref "P11") (pin "3") (pinfunction "3_3") (pintype "passive"))
      (node (ref "P12") (pin "3") (pinfunction "3_3") (pintype "passive"))
      (node (ref "P13") (pin "3") (pinfunction "3_3") (pintype "passive"))
      (node (ref "P14") (pin "3") (pinfunction "3_3") (pintype "passive"))
      (node (ref "P15") (pin "3") (pinfunction "3_3") (pintype "passive"))
      (node (ref "P16") (pin "3") (pinfunction "3_3") (pintype "passive"))
      (node (ref "P17") (pin "3") (pinfunction "3_3") (pintype "passive"))
      (node (ref "P18") (pin "3") (pinfunction "3_3") (pintype "passive"))
      (node (ref "P2") (pin "2") (pinfunction "2_2") (pintype "passive"))
      (node (ref "P2") (pin "5") (pinfunction "5_5") (pintype "passive"))
      (node (ref "P3") (pin "3") (pinfunction "3_3") (pintype "passive"))
      (node (ref "P4") (pin "3") (pinfunction "3_3") (pintype "passive"))
      (node (ref "P5") (pin "3") (pinfunction "3_3") (pintype "passive"))
      (node (ref "P6") (pin "3") (pinfunction "3_3") (pintype "passive"))
      (node (ref "P7") (pin "3") (pinfunction "3_3") (pintype "passive"))
      (node (ref "P8") (pin "3") (pinfunction "3_3") (pintype "passive"))
      (node (ref "P9") (pin "3") (pinfunction "3_3") (pintype "passive"))
      (node (ref "Q1") (pin "2") (pinfunction "2_2") (pintype "passive"))
      (node (ref "Q3") (pin "2") (pinfunction "2_2") (pintype "passive"))
      (node (ref "R18") (pin "2") (pinfunction "2_2") (pintype "passive"))
      (node (ref "R19") (pin "2") (pinfunction "2_2") (pintype "passive"))
      (node (ref "R20") (pin "2") (pinfunction "2_2") (pintype "passive"))
      (node (ref "R26") (pin "1") (pinfunction "1_1") (pintype "passive"))
      (node (ref "R27") (pin "1") (pinfunction "1_1") (pintype "passive"))
      (node (ref "R28") (pin "2") (pinfunction "2_2") (pintype "passive"))
      (node (ref "R29") (pin "2") (pinfunction "2_2") (pintype "passive"))
      (node (ref "R7") (pin "2") (pinfunction "2_2") (pintype "passive"))
      (node (ref "R8") (pin "2") (pinfunction "2_2") (pintype "passive"))
      (node (ref "U1") (pin "3") (pinfunction "P0_3") (pintype "input"))
      (node (ref "U1") (pin "4") (pinfunction "P1_4") (pintype "input"))
      (node (ref "U1") (pin "5") (pinfunction "P2_5") (pintype "input"))
      (node (ref "U1") (pin "6") (pinfunction "P3_6") (pintype "input"))
      (node (ref "U1") (pin "8") (pinfunction "GND_8") (pintype "power_in"))
      (node (ref "U10") (pin "1") (pinfunction "GND_1") (pintype "power_in"))
      (node (ref "U11") (pin "4") (pinfunction "V-_4") (pintype "power_in"))
      (node (ref "U12") (pin "4") (pinfunction "V-_4") (pintype "power_in"))
      (node (ref "U12") (pin "5") (pinfunction "+INB_5") (pintype "input"))
      (node (ref "U12") (pin "6") (pinfunction "-INB_6") (pintype "input"))
      (node (ref "U12") (pin "7") (pinfunction "OUTB_7") (pintype "output"))
      (node (ref "U13") (pin "14") (pinfunction "GND_14") (pintype "power_in"))
      (node (ref "U14") (pin "14") (pinfunction "GND_14") (pintype "power_in"))
      (node (ref "U2") (pin "1") (pinfunction "GND_1") (pintype "power_in"))
      (node (ref "U3") (pin "14") (pinfunction "GND_14") (pintype "power_in"))
      (node (ref "U4") (pin "14") (pinfunction "GND_14") (pintype "power_in"))
      (node (ref "U7") (pin "2") (pinfunction "GND_2") (pintype "power_in"))
      (node (ref "VR1") (pin "2") (pinfunction "GND_2") (pintype "passive"))
    )
    (net (code "41") (name "Net-(C9-Pad1)") (class "Default")
      (node (ref "C9") (pin "1") (pinfunction "1_1") (pintype "passive"))
      (node (ref "R11") (pin "2") (pinfunction "2_2") (pintype "passive"))
      (node (ref "R14") (pin "2") (pinfunction "2_2") (pintype "passive"))
    )
    (net (code "42") (name "Net-(C12-Pad1)") (class "Default")
      (node (ref "C12") (pin "1") (pinfunction "1_1") (pintype "passive"))
      (node (ref "R17") (pin "1") (pinfunction "1_1") (pintype "passive"))
    )
    (net (code "43") (name "Net-(C12-Pad2)") (class "Default")
      (node (ref "C12") (pin "2") (pinfunction "2_2") (pintype "passive"))
      (node (ref "Q2") (pin "3") (pinfunction "3_3") (pintype "passive"))
      (node (ref "R15") (pin "2") (pinfunction "2_2") (pintype "passive"))
    )
    (net (code "44") (name "Net-(C13-Pad2)") (class "Default")
      (node (ref "C13") (pin "2") (pinfunction "2_2") (pintype "passive"))
      (node (ref "C17") (pin "2") (pinfunction "2_2") (pintype "passive"))
      (node (ref "R5") (pin "1") (pinfunction "1_1") (pintype "passive"))
    )
    (net (code "45") (name "Net-(C14-Pad1)") (class "Default")
      (node (ref "C14") (pin "1") (pinfunction "1_1") (pintype "passive"))
      (node (ref "Q2") (pin "1") (pinfunction "1_1") (pintype "passive"))
      (node (ref "R16") (pin "2") (pinfunction "2_2") (pintype "passive"))
      (node (ref "R18") (pin "1") (pinfunction "1_1") (pintype "passive"))
    )
    (net (code "46") (name "Net-(D1-CATHODE)") (class "Default")
      (node (ref "D1") (pin "3") (pinfunction "CATHODE_3") (pintype "output"))
      (node (ref "R23") (pin "2") (pinfunction "2_2") (pintype "passive"))
      (node (ref "R24") (pin "1") (pinfunction "1_1") (pintype "passive"))
      (node (ref "R26") (pin "2") (pinfunction "2_2") (pintype "passive"))
    )
    (net (code "47") (name "Net-(P1-Pad1)") (class "Default")
      (node (ref "P1") (pin "1") (pinfunction "1_1") (pintype "passive"))
      (node (ref "P2") (pin "1") (pinfunction "1_1") (pintype "passive"))
    )
    (net (code "48") (name "Net-(Q1-Pad1)") (class "Default")
      (node (ref "Q1") (pin "1") (pinfunction "1_1") (pintype "passive"))
      (node (ref "R4") (pin "2") (pinfunction "2_2") (pintype "passive"))
    )
    (net (code "49") (name "Net-(Q2-Pad2)") (class "Default")
      (node (ref "Q2") (pin "2") (pinfunction "2_2") (pintype "passive"))
      (node (ref "R19") (pin "1") (pinfunction "1_1") (pintype "passive"))
    )
    (net (code "50") (name "Net-(U1-CLK)") (class "Default")
      (node (ref "R2") (pin "2") (pinfunction "2_2") (pintype "passive"))
      (node (ref "U1") (pin "2") (pinfunction "CLK_2") (pintype "input"))
      (node (ref "U2") (pin "3") (pinfunction "OUT_3") (pintype "output"))
    )
    (net (code "51") (name "Net-(U2-CVOLT)") (class "Default")
      (node (ref "C2") (pin "2") (pinfunction "2_2") (pintype "passive"))
      (node (ref "U2") (pin "5") (pinfunction "CVOLT_5") (pintype "passive"))
    )
    (net (code "52") (name "Net-(U2-THR)") (class "Default")
      (node (ref "C1") (pin "2") (pinfunction "2_2") (pintype "passive"))
      (node (ref "R1") (pin "1") (pinfunction "1_1") (pintype "passive"))
      (node (ref "R2") (pin "1") (pinfunction "1_1") (pintype "passive"))
      (node (ref "U2") (pin "2") (pinfunction "TRIG_2") (pintype "input"))
      (node (ref "U2") (pin "6") (pinfunction "THR_6") (pintype "input"))
    )
    (net (code "53") (name "Net-(U3-D)") (class "Default")
      (node (ref "R5") (pin "2") (pinfunction "2_2") (pintype "passive"))
      (node (ref "U3") (pin "8") (pinfunction "D_8") (pintype "bidirectional"))
      (node (ref "U4") (pin "8") (pinfunction "D_8") (pintype "bidirectional"))
    )
    (net (code "54") (name "Net-(U5-IN+)") (class "Default")
      (node (ref "C13") (pin "1") (pinfunction "1_1") (pintype "passive"))
      (node (ref "R7") (pin "1") (pinfunction "1_1") (pintype "passive"))
      (node (ref "U5") (pin "3") (pinfunction "IN+_3") (pintype "input"))
    )
    (net (code "55") (name "Net-(U5-IN-)") (class "Default")
      (node (ref "R6") (pin "2") (pinfunction "2_2") (pintype "passive"))
      (node (ref "R8") (pin "1") (pinfunction "1_1") (pintype "passive"))
      (node (ref "U5") (pin "2") (pinfunction "IN-_2") (pintype "input"))
    )
    (net (code "56") (name "Net-(U5-OUT)") (class "Default")
      (node (ref "C14") (pin "2") (pinfunction "2_2") (pintype "passive"))
      (node (ref "R6") (pin "1") (pinfunction "1_1") (pintype "passive"))
      (node (ref "U5") (pin "6") (pinfunction "OUT_6") (pintype "output"))
    )
    (net (code "57") (name "Net-(U6-IN+)") (class "Default")
      (node (ref "C4") (pin "1") (pinfunction "1_1") (pintype "passive"))
      (node (ref "R11") (pin "1") (pinfunction "1_1") (pintype "passive"))
      (node (ref "U6") (pin "3") (pinfunction "IN+_3") (pintype "input"))
    )
    (net (code "58") (name "Net-(U6-IN-)") (class "Default")
      (node (ref "R14") (pin "1") (pinfunction "1_1") (pintype "passive"))
      (node (ref "R9") (pin "2") (pinfunction "2_2") (pintype "passive"))
      (node (ref "U6") (pin "2") (pinfunction "IN-_2") (pintype "input"))
    )
    (net (code "59") (name "Net-(U6-OUT)") (class "Default")
      (node (ref "R12") (pin "1") (pinfunction "1_1") (pintype "passive"))
      (node (ref "R9") (pin "1") (pinfunction "1_1") (pintype "passive"))
      (node (ref "U6") (pin "6") (pinfunction "OUT_6") (pintype "output"))
    )
    (net (code "60") (name "Net-(U8-IN+)") (class "Default")
      (node (ref "R12") (pin "2") (pinfunction "2_2") (pintype "passive"))
      (node (ref "R17") (pin "2") (pinfunction "2_2") (pintype "passive"))
      (node (ref "U8") (pin "3") (pinfunction "IN+_3") (pintype "input"))
    )
    (net (code "61") (name "Net-(U8-IN-)") (class "Default")
      (node (ref "R13") (pin "2") (pinfunction "2_2") (pintype "passive"))
      (node (ref "R20") (pin "1") (pinfunction "1_1") (pintype "passive"))
      (node (ref "U8") (pin "2") (pinfunction "IN-_2") (pintype "input"))
    )
    (net (code "62") (name "Net-(U9-C1)") (class "Default")
      (node (ref "R21") (pin "1") (pinfunction "1_1") (pintype "passive"))
      (node (ref "U9") (pin "6") (pinfunction "C1_6") (pintype "passive"))
    )
    (net (code "63") (name "Net-(U9-C2)") (class "Default")
      (node (ref "R22") (pin "2") (pinfunction "2_2") (pintype "passive"))
      (node (ref "U9") (pin "3") (pinfunction "C2_3") (pintype "passive"))
    )
    (net (code "64") (name "Net-(U10-VOUT)") (class "Default")
      (node (ref "C19") (pin "2") (pinfunction "2_2") (pintype "passive"))
      (node (ref "U10") (pin "2") (pinfunction "VOUT_2") (pintype "output"))
      (node (ref "U12") (pin "3") (pinfunction "+INA_3") (pintype "input"))
    )
    (net (code "65") (name "Net-(U11-+INA)") (class "Default")
      (node (ref "R24") (pin "2") (pinfunction "2_2") (pintype "passive"))
      (node (ref "U11") (pin "3") (pinfunction "+INA_3") (pintype "input"))
    )
    (net (code "66") (name "Net-(U11-+INB)") (class "Default")
      (node (ref "C22") (pin "1") (pinfunction "1_1") (pintype "passive"))
      (node (ref "R29") (pin "1") (pinfunction "1_1") (pintype "passive"))
      (node (ref "U11") (pin "5") (pinfunction "+INB_5") (pintype "input"))
      (node (ref "U9") (pin "4") (pinfunction "E2_4") (pintype "passive"))
    )
    (net (code "67") (name "Net-(U11--INA)") (class "Default")
      (node (ref "R27") (pin "2") (pinfunction "2_2") (pintype "passive"))
      (node (ref "U11") (pin "2") (pinfunction "-INA_2") (pintype "input"))
      (node (ref "U9") (pin "1") (pinfunction "E1_1") (pintype "passive"))
    )
    (net (code "68") (name "Net-(U11--INB)") (class "Default")
      (node (ref "R25") (pin "2") (pinfunction "2_2") (pintype "passive"))
      (node (ref "R28") (pin "1") (pinfunction "1_1") (pintype "passive"))
      (node (ref "U11") (pin "6") (pinfunction "-INB_6") (pintype "input"))
    )
    (net (code "69") (name "Net-(U11-OUTA)") (class "Default")
      (node (ref "U11") (pin "1") (pinfunction "OUTA_1") (pintype "output"))
      (node (ref "U9") (pin "2") (pinfunction "B1_2") (pintype "passive"))
      (node (ref "U9") (pin "5") (pinfunction "B2_5") (pintype "passive"))
    )
    (net (code "70") (name "Net-(U11-OUTB)") (class "Default")
      (node (ref "R25") (pin "1") (pinfunction "1_1") (pintype "passive"))
      (node (ref "U11") (pin "7") (pinfunction "OUTB_7") (pintype "output"))
      (node (ref "U12") (pin "2") (pinfunction "-INA_2") (pintype "input"))
    )
    (net (code "71") (name "Net-(U12-OUTA)") (class "Default")
      (node (ref "Q3") (pin "1") (pinfunction "1_1") (pintype "passive"))
      (node (ref "U12") (pin "1") (pinfunction "OUTA_1") (pintype "output"))
    )
    (net (code "72") (name "Net-(U13-D)") (class "Default")
      (node (ref "Q3") (pin "3") (pinfunction "3_3") (pintype "passive"))
      (node (ref "R30") (pin "2") (pinfunction "2_2") (pintype "passive"))
      (node (ref "U13") (pin "8") (pinfunction "D_8") (pintype "bidirectional"))
      (node (ref "U14") (pin "8") (pinfunction "D_8") (pintype "bidirectional"))
    )
    (net (code "73") (name "unconnected-(P2-Pad3)") (class "Default")
      (node (ref "P2") (pin "3") (pinfunction "3_3") (pintype "passive"))
    )
    (net (code "74") (name "unconnected-(P2-Pad7)") (class "Default")
      (node (ref "P2") (pin "7") (pinfunction "7_7") (pintype "passive"))
    )
    (net (code "75") (name "unconnected-(U1-TC-Pad15)") (class "Default")
      (node (ref "U1") (pin "15") (pinfunction "TC_15") (pintype "output"))
    )
    (net (code "76") (name "unconnected-(U2-DISC-Pad7)") (class "Default")
      (node (ref "U2") (pin "7") (pinfunction "DISC_7") (pintype "open_collector"))
    )
    (net (code "77") (name "unconnected-(U4-S5-Pad12)") (class "Default")
      (node (ref "U4") (pin "12") (pinfunction "S5_12") (pintype "bidirectional"))
    )
    (net (code "78") (name "unconnected-(U4-S6-Pad11)") (class "Default")
      (node (ref "U4") (pin "11") (pinfunction "S6_11") (pintype "bidirectional"))
    )
    (net (code "79") (name "unconnected-(U4-S7-Pad10)") (class "Default")
      (node (ref "U4") (pin "10") (pinfunction "S7_10") (pintype "bidirectional"))
    )
    (net (code "80") (name "unconnected-(U4-S8-Pad9)") (class "Default")
      (node (ref "U4") (pin "9") (pinfunction "S8_9") (pintype "bidirectional"))
    )
    (net (code "81") (name "unconnected-(U5-NC-Pad1)") (class "Default")
      (node (ref "U5") (pin "1") (pinfunction "NC_1") (pintype "passive"))
    )
    (net (code "82") (name "unconnected-(U5-NC-Pad5)") (class "Default")
      (node (ref "U5") (pin "5") (pinfunction "NC_5") (pintype "passive"))
    )
    (net (code "83") (name "unconnected-(U5-NC-Pad8)") (class "Default")
      (node (ref "U5") (pin "8") (pinfunction "NC_8") (pintype "passive"))
    )
    (net (code "84") (name "unconnected-(U6-NC-Pad1)") (class "Default")
      (node (ref "U6") (pin "1") (pinfunction "NC_1") (pintype "passive"))
    )
    (net (code "85") (name "unconnected-(U6-NC-Pad5)") (class "Default")
      (node (ref "U6") (pin "5") (pinfunction "NC_5") (pintype "passive"))
    )
    (net (code "86") (name "unconnected-(U6-NC-Pad8)") (class "Default")
      (node (ref "U6") (pin "8") (pinfunction "NC_8") (pintype "passive"))
    )
    (net (code "87") (name "unconnected-(U7-REF-Pad1)") (class "Default")
      (node (ref "U7") (pin "1") (pinfunction "REF_1") (pintype "passive"))
    )
    (net (code "88") (name "unconnected-(U8-NC-Pad1)") (class "Default")
      (node (ref "U8") (pin "1") (pinfunction "NC_1") (pintype "passive"))
    )
    (net (code "89") (name "unconnected-(U8-NC-Pad5)") (class "Default")
      (node (ref "U8") (pin "5") (pinfunction "NC_5") (pintype "passive"))
    )
    (net (code "90") (name "unconnected-(U8-NC-Pad8)") (class "Default")
      (node (ref "U8") (pin "8") (pinfunction "NC_8") (pintype "passive"))
    )
    (net (code "91") (name "unconnected-(U14-S5-Pad12)") (class "Default")
      (node (ref "U14") (pin "12") (pinfunction "S5_12") (pintype "bidirectional"))
    )
    (net (code "92") (name "unconnected-(U14-S6-Pad11)") (class "Default")
      (node (ref "U14") (pin "11") (pinfunction "S6_11") (pintype "bidirectional"))
    )
    (net (code "93") (name "unconnected-(U14-S7-Pad10)") (class "Default")
      (node (ref "U14") (pin "10") (pinfunction "S7_10") (pintype "bidirectional"))
    )
    (net (code "94") (name "unconnected-(U14-S8-Pad9)") (class "Default")
      (node (ref "U14") (pin "9") (pinfunction "S8_9") (pintype "bidirectional"))
    )
  )
)
